# atx_form_card.net
KiCad netlist of a schematic drawn in EAGLE
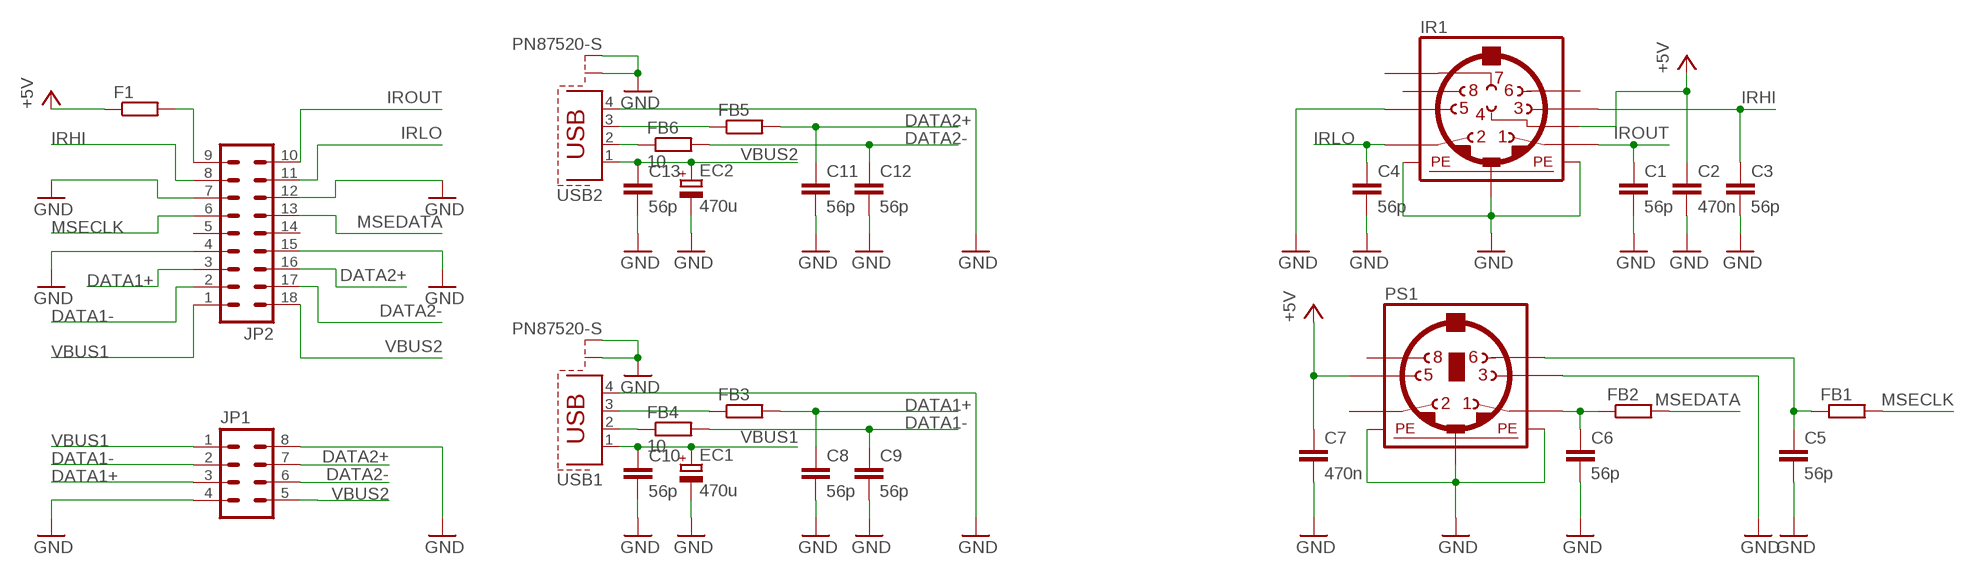
[diagram p0: schematic, sheet 1]

(export (version "E")
  (design (tool "Eeschema 10.0.6"))
  (components
    (comp (ref "C1")
      (value "56p")
      (footprint "eagle-import:C3216")
      (libsource (lib "eagle-import") (part "C-EUC3216"))
    )
    (comp (ref "C2")
      (value "470n")
      (footprint "eagle-import:C3216")
      (libsource (lib "eagle-import") (part "C-EUC3216"))
    )
    (comp (ref "C3")
      (value "56p")
      (footprint "eagle-import:C3216")
      (libsource (lib "eagle-import") (part "C-EUC3216"))
    )
    (comp (ref "C4")
      (value "56p")
      (footprint "eagle-import:C3216")
      (libsource (lib "eagle-import") (part "C-EUC3216"))
    )
    (comp (ref "C5")
      (value "56p")
      (footprint "eagle-import:C3216")
      (libsource (lib "eagle-import") (part "C-EUC3216"))
    )
    (comp (ref "C6")
      (value "56p")
      (footprint "eagle-import:C3216")
      (libsource (lib "eagle-import") (part "C-EUC3216"))
    )
    (comp (ref "C7")
      (value "470n")
      (footprint "eagle-import:C3216")
      (libsource (lib "eagle-import") (part "C-EUC3216"))
    )
    (comp (ref "C8")
      (value "56p")
      (footprint "eagle-import:C3216")
      (libsource (lib "eagle-import") (part "C-EUC3216"))
    )
    (comp (ref "C9")
      (value "56p")
      (footprint "eagle-import:C3216")
      (libsource (lib "eagle-import") (part "C-EUC3216"))
    )
    (comp (ref "C10")
      (value "56p")
      (footprint "eagle-import:C3216")
      (libsource (lib "eagle-import") (part "C-EUC3216"))
    )
    (comp (ref "C11")
      (value "56p")
      (footprint "eagle-import:C3216")
      (libsource (lib "eagle-import") (part "C-EUC3216"))
    )
    (comp (ref "C12")
      (value "56p")
      (footprint "eagle-import:C3216")
      (libsource (lib "eagle-import") (part "C-EUC3216"))
    )
    (comp (ref "C13")
      (value "56p")
      (footprint "eagle-import:C3216")
      (libsource (lib "eagle-import") (part "C-EUC3216"))
    )
    (comp (ref "EC1")
      (value "470u")
      (footprint "eagle-import:E3,5-8")
      (libsource (lib "eagle-import") (part "CPOL-EUE3.5-8"))
    )
    (comp (ref "EC2")
      (value "470u")
      (footprint "eagle-import:E3,5-8")
      (libsource (lib "eagle-import") (part "CPOL-EUE3.5-8"))
    )
    (comp (ref "F1")
      (value "R-EU_0207/10")
      (footprint "eagle-import:0207_10")
      (libsource (lib "eagle-import") (part "R-EU_0207/10"))
    )
    (comp (ref "FB1")
      (value "R-EU_M3216")
      (footprint "eagle-import:M3216")
      (libsource (lib "eagle-import") (part "R-EU_M3216"))
    )
    (comp (ref "FB2")
      (value "R-EU_M3216")
      (footprint "eagle-import:M3216")
      (libsource (lib "eagle-import") (part "R-EU_M3216"))
    )
    (comp (ref "FB3")
      (value "R-EU_M3216")
      (footprint "eagle-import:M3216")
      (libsource (lib "eagle-import") (part "R-EU_M3216"))
    )
    (comp (ref "FB4")
      (value "10")
      (footprint "eagle-import:M3216")
      (libsource (lib "eagle-import") (part "R-EU_M3216"))
    )
    (comp (ref "FB5")
      (value "R-EU_M3216")
      (footprint "eagle-import:M3216")
      (libsource (lib "eagle-import") (part "R-EU_M3216"))
    )
    (comp (ref "FB6")
      (value "10")
      (footprint "eagle-import:M3216")
      (libsource (lib "eagle-import") (part "R-EU_M3216"))
    )
    (comp (ref "IR1")
      (value "MINI_DIN_8")
      (footprint "eagle-import:M_DIN8")
      (libsource (lib "eagle-import") (part "MINI_DIN_8"))
    )
    (comp (ref "JP1")
      (value "MA04-2")
      (footprint "eagle-import:MA04-2")
      (libsource (lib "eagle-import") (part "MA04-2"))
    )
    (comp (ref "JP2")
      (value "MA09-2")
      (footprint "eagle-import:MA09-2")
      (libsource (lib "eagle-import") (part "MA09-2"))
    )
    (comp (ref "PS1")
      (value "MINI_DIN_6")
      (footprint "eagle-import:M_DIN6")
      (libsource (lib "eagle-import") (part "MINI_DIN_6"))
    )
    (comp (ref "USB1")
      (value "PN87520-S")
      (footprint "eagle-import:PN87520-S")
      (libsource (lib "eagle-import") (part "PN87520-S"))
    )
    (comp (ref "USB2")
      (value "PN87520-S")
      (footprint "eagle-import:PN87520-S")
      (libsource (lib "eagle-import") (part "PN87520-S"))
    )
  )
  (nets
    (net (code "1") (name "+5V") (class "Default")
      (node (ref "C2") (pin "1") (pinfunction "1_1") (pintype "passive"))
      (node (ref "C7") (pin "1") (pinfunction "1_1") (pintype "passive"))
      (node (ref "F1") (pin "1") (pinfunction "1_1") (pintype "passive"))
      (node (ref "IR1") (pin "4") (pinfunction "4_4") (pintype "passive"))
      (node (ref "PS1") (pin "5") (pinfunction "5_5") (pintype "passive"))
    )
    (net (code "2") (name "/DATA1+") (class "Default")
      (node (ref "C8") (pin "1") (pinfunction "1_1") (pintype "passive"))
      (node (ref "FB3") (pin "2") (pinfunction "2_2") (pintype "passive"))
      (node (ref "JP1") (pin "3") (pinfunction "3_3") (pintype "passive"))
      (node (ref "JP2") (pin "3") (pinfunction "3__3") (pintype "passive"))
    )
    (net (code "3") (name "/DATA1-") (class "Default")
      (node (ref "C9") (pin "1") (pinfunction "1_1") (pintype "passive"))
      (node (ref "FB4") (pin "2") (pinfunction "2_2") (pintype "passive"))
      (node (ref "JP1") (pin "2") (pinfunction "2_2") (pintype "passive"))
      (node (ref "JP2") (pin "2") (pinfunction "2__2") (pintype "passive"))
    )
    (net (code "4") (name "/DATA2+") (class "Default")
      (node (ref "C11") (pin "1") (pinfunction "1_1") (pintype "passive"))
      (node (ref "FB5") (pin "2") (pinfunction "2_2") (pintype "passive"))
      (node (ref "JP1") (pin "7") (pinfunction "7_7") (pintype "passive"))
      (node (ref "JP2") (pin "16") (pinfunction "12__16") (pintype "passive"))
    )
    (net (code "5") (name "/DATA2-") (class "Default")
      (node (ref "C12") (pin "1") (pinfunction "1_1") (pintype "passive"))
      (node (ref "FB6") (pin "2") (pinfunction "2_2") (pintype "passive"))
      (node (ref "JP1") (pin "6") (pinfunction "6_6") (pintype "passive"))
      (node (ref "JP2") (pin "17") (pinfunction "11__17") (pintype "passive"))
    )
    (net (code "6") (name "/IRHI") (class "Default")
      (node (ref "C3") (pin "1") (pinfunction "1_1") (pintype "passive"))
      (node (ref "IR1") (pin "3") (pinfunction "3_3") (pintype "passive"))
      (node (ref "JP2") (pin "8") (pinfunction "8__8") (pintype "passive"))
    )
    (net (code "7") (name "/IRLO") (class "Default")
      (node (ref "C4") (pin "1") (pinfunction "1_1") (pintype "passive"))
      (node (ref "IR1") (pin "2") (pinfunction "2_2") (pintype "passive"))
      (node (ref "JP2") (pin "11") (pinfunction "17__11") (pintype "passive"))
    )
    (net (code "8") (name "/IROUT") (class "Default")
      (node (ref "C1") (pin "1") (pinfunction "1_1") (pintype "passive"))
      (node (ref "IR1") (pin "1") (pinfunction "1_1") (pintype "passive"))
      (node (ref "JP2") (pin "10") (pinfunction "18__10") (pintype "passive"))
    )
    (net (code "9") (name "/MSECLK") (class "Default")
      (node (ref "FB1") (pin "2") (pinfunction "2_2") (pintype "passive"))
      (node (ref "JP2") (pin "6") (pinfunction "6__6") (pintype "passive"))
    )
    (net (code "10") (name "/MSEDATA") (class "Default")
      (node (ref "FB2") (pin "2") (pinfunction "2_2") (pintype "passive"))
      (node (ref "JP2") (pin "13") (pinfunction "15__13") (pintype "passive"))
    )
    (net (code "11") (name "/VBUS1") (class "Default")
      (node (ref "C10") (pin "1") (pinfunction "1_1") (pintype "passive"))
      (node (ref "EC1") (pin "+") (pinfunction "+_+") (pintype "passive"))
      (node (ref "JP1") (pin "1") (pinfunction "1_1") (pintype "passive"))
      (node (ref "JP2") (pin "1") (pinfunction "1__1") (pintype "passive"))
      (node (ref "USB1") (pin "1") (pinfunction "1_1") (pintype "passive"))
    )
    (net (code "12") (name "/VBUS2") (class "Default")
      (node (ref "C13") (pin "1") (pinfunction "1_1") (pintype "passive"))
      (node (ref "EC2") (pin "+") (pinfunction "+_+") (pintype "passive"))
      (node (ref "JP1") (pin "5") (pinfunction "5_5") (pintype "passive"))
      (node (ref "JP2") (pin "18") (pinfunction "10__18") (pintype "passive"))
      (node (ref "USB2") (pin "1") (pinfunction "1_1") (pintype "passive"))
    )
    (net (code "13") (name "GND") (class "Default")
      (node (ref "C1") (pin "2") (pinfunction "2_2") (pintype "passive"))
      (node (ref "C10") (pin "2") (pinfunction "2_2") (pintype "passive"))
      (node (ref "C11") (pin "2") (pinfunction "2_2") (pintype "passive"))
      (node (ref "C12") (pin "2") (pinfunction "2_2") (pintype "passive"))
      (node (ref "C13") (pin "2") (pinfunction "2_2") (pintype "passive"))
      (node (ref "C2") (pin "2") (pinfunction "2_2") (pintype "passive"))
      (node (ref "C3") (pin "2") (pinfunction "2_2") (pintype "passive"))
      (node (ref "C4") (pin "2") (pinfunction "2_2") (pintype "passive"))
      (node (ref "C5") (pin "2") (pinfunction "2_2") (pintype "passive"))
      (node (ref "C6") (pin "2") (pinfunction "2_2") (pintype "passive"))
      (node (ref "C7") (pin "2") (pinfunction "2_2") (pintype "passive"))
      (node (ref "C8") (pin "2") (pinfunction "2_2") (pintype "passive"))
      (node (ref "C9") (pin "2") (pinfunction "2_2") (pintype "passive"))
      (node (ref "EC1") (pin "-") (pinfunction "-_-") (pintype "passive"))
      (node (ref "EC2") (pin "-") (pinfunction "-_-") (pintype "passive"))
      (node (ref "IR1") (pin "5") (pinfunction "5_5") (pintype "passive"))
      (node (ref "IR1") (pin "SH1") (pinfunction "PE1_SH1") (pintype "power_in"))
      (node (ref "IR1") (pin "SH2") (pinfunction "PE2_SH2") (pintype "power_in"))
      (node (ref "IR1") (pin "SH3") (pinfunction "PE3_SH3") (pintype "power_in"))
      (node (ref "JP1") (pin "4") (pinfunction "4_4") (pintype "passive"))
      (node (ref "JP1") (pin "8") (pinfunction "8_8") (pintype "passive"))
      (node (ref "JP2") (pin "12") (pinfunction "16__12") (pintype "passive"))
      (node (ref "JP2") (pin "15") (pinfunction "13__15") (pintype "passive"))
      (node (ref "JP2") (pin "4") (pinfunction "4__4") (pintype "passive"))
      (node (ref "JP2") (pin "7") (pinfunction "7__7") (pintype "passive"))
      (node (ref "PS1") (pin "3") (pinfunction "3_3") (pintype "passive"))
      (node (ref "PS1") (pin "SH1") (pinfunction "PE1_SH1") (pintype "power_in"))
      (node (ref "PS1") (pin "SH2") (pinfunction "PE2_SH2") (pintype "power_in"))
      (node (ref "PS1") (pin "SH3") (pinfunction "PE3_SH3") (pintype "power_in"))
      (node (ref "USB1") (pin "4") (pinfunction "4_4") (pintype "passive"))
      (node (ref "USB1") (pin "S1") (pinfunction "S1_S1") (pintype "passive"))
      (node (ref "USB1") (pin "S2") (pinfunction "S2_S2") (pintype "passive"))
      (node (ref "USB2") (pin "4") (pinfunction "4_4") (pintype "passive"))
      (node (ref "USB2") (pin "S1") (pinfunction "S1_S1") (pintype "passive"))
      (node (ref "USB2") (pin "S2") (pinfunction "S2_S2") (pintype "passive"))
    )
    (net (code "14") (name "Net-(C5-Pad1)") (class "Default")
      (node (ref "C5") (pin "1") (pinfunction "1_1") (pintype "passive"))
      (node (ref "FB1") (pin "1") (pinfunction "1_1") (pintype "passive"))
      (node (ref "PS1") (pin "6") (pinfunction "6_6") (pintype "passive"))
    )
    (net (code "15") (name "Net-(C6-Pad1)") (class "Default")
      (node (ref "C6") (pin "1") (pinfunction "1_1") (pintype "passive"))
      (node (ref "FB2") (pin "1") (pinfunction "1_1") (pintype "passive"))
      (node (ref "PS1") (pin "1") (pinfunction "1_1") (pintype "passive"))
    )
    (net (code "16") (name "Net-(FB3-Pad1)") (class "Default")
      (node (ref "FB3") (pin "1") (pinfunction "1_1") (pintype "passive"))
      (node (ref "USB1") (pin "3") (pinfunction "3_3") (pintype "passive"))
    )
    (net (code "17") (name "Net-(FB4-Pad1)") (class "Default")
      (node (ref "FB4") (pin "1") (pinfunction "1_1") (pintype "passive"))
      (node (ref "USB1") (pin "2") (pinfunction "2_2") (pintype "passive"))
    )
    (net (code "18") (name "Net-(FB5-Pad1)") (class "Default")
      (node (ref "FB5") (pin "1") (pinfunction "1_1") (pintype "passive"))
      (node (ref "USB2") (pin "3") (pinfunction "3_3") (pintype "passive"))
    )
    (net (code "19") (name "Net-(FB6-Pad1)") (class "Default")
      (node (ref "FB6") (pin "1") (pinfunction "1_1") (pintype "passive"))
      (node (ref "USB2") (pin "2") (pinfunction "2_2") (pintype "passive"))
    )
    (net (code "20") (name "Net-(JP2-9_)") (class "Default")
      (node (ref "F1") (pin "2") (pinfunction "2_2") (pintype "passive"))
      (node (ref "JP2") (pin "9") (pinfunction "9__9") (pintype "passive"))
    )
    (net (code "21") (name "unconnected-(IR1-Pad6)") (class "Default")
      (node (ref "IR1") (pin "6") (pinfunction "6_6") (pintype "passive"))
    )
    (net (code "22") (name "unconnected-(IR1-Pad7)") (class "Default")
      (node (ref "IR1") (pin "7") (pinfunction "7_7") (pintype "passive"))
    )
    (net (code "23") (name "unconnected-(IR1-Pad8)") (class "Default")
      (node (ref "IR1") (pin "8") (pinfunction "8_8") (pintype "passive"))
    )
    (net (code "24") (name "unconnected-(JP2-5_-Pad5)") (class "Default")
      (node (ref "JP2") (pin "5") (pinfunction "5__5") (pintype "passive"))
    )
    (net (code "25") (name "unconnected-(JP2-14_-Pad14)") (class "Default")
      (node (ref "JP2") (pin "14") (pinfunction "14__14") (pintype "passive"))
    )
    (net (code "26") (name "unconnected-(PS1-Pad2)") (class "Default")
      (node (ref "PS1") (pin "2") (pinfunction "2_2") (pintype "passive"))
    )
    (net (code "27") (name "unconnected-(PS1-Pad8)") (class "Default")
      (node (ref "PS1") (pin "8") (pinfunction "8_8") (pintype "passive"))
    )
  )
)
